# IMD.net
KiCad netlist of a schematic drawn in Altium Designer
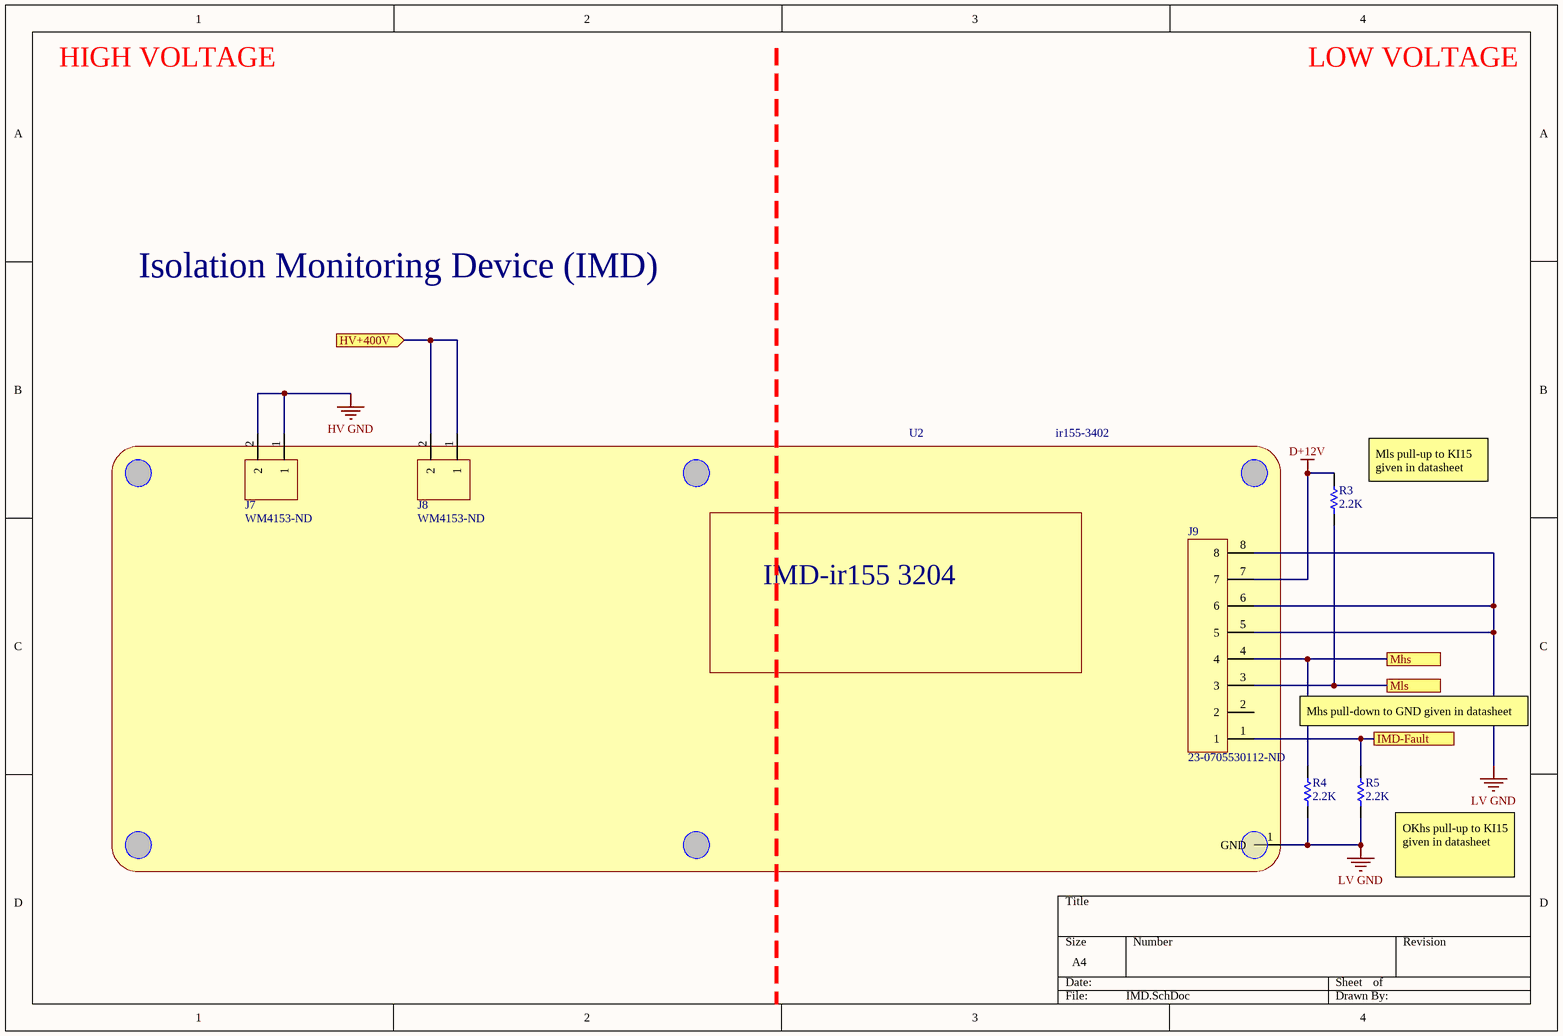
[diagram p0: IMD.SchDoc]

(export (version "E")
  (design (tool "Eeschema 10.0.6"))
  (components
    (comp (ref "J7")
      (value "WM4153-ND")
      (footprint "2PIN")
      (description "CONN HEADER R/A 2POS 2.54MM")
      (fields (field (name "MANUFACTURER") "Molex") (field (name "MANUFACTURER PART NUMBER") "0705530106"))
      (libsource (lib "Connectors") (part "2PIN"))
    )
    (comp (ref "J8")
      (value "WM4153-ND")
      (footprint "2PIN")
      (description "CONN HEADER R/A 2POS 2.54MM")
      (fields (field (name "MANUFACTURER") "Molex") (field (name "MANUFACTURER PART NUMBER") "0705530106"))
      (libsource (lib "Connectors") (part "2PIN"))
    )
    (comp (ref "J9")
      (value "23-0705530112-ND")
      (footprint "8PIN")
      (description "CONN HEADER R/A 8POS 2.54MM")
      (fields (field (name "MANUFACTURER") "Molex") (field (name "MANUFACTURER PART NUMBER") "70553-0112"))
      (libsource (lib "Connectors") (part "8PIN"))
    )
    (comp (ref "R3")
      (value "2.2K")
      (footprint "RES-0805")
      (description "RES SMD 2.2K OHM 1% 1/8W 0805")
      (fields
        (field (name "MANUFACTURER") "Yageo")
        (field (name "MANUFACTURER PART NUMBER") "RC0805FR-072K2L")
      )
      (libsource (lib "Resistors") (part "0805-2.2KR"))
    )
    (comp (ref "R4")
      (value "2.2K")
      (footprint "RES-0805")
      (description "RES SMD 2.2K OHM 1% 1/8W 0805")
      (fields
        (field (name "MANUFACTURER") "Yageo")
        (field (name "MANUFACTURER PART NUMBER") "RC0805FR-072K2L")
      )
      (libsource (lib "Resistors") (part "0805-2.2KR"))
    )
    (comp (ref "R5")
      (value "2.2K")
      (footprint "RES-0805")
      (description "RES SMD 2.2K OHM 1% 1/8W 0805")
      (fields
        (field (name "MANUFACTURER") "Yageo")
        (field (name "MANUFACTURER PART NUMBER") "RC0805FR-072K2L")
      )
      (libsource (lib "Resistors") (part "0805-2.2KR"))
    )
    (comp (ref "U2")
      (value "ir155-3402")
      (footprint "IMD-Bender ir155 3204")
      (libsource (lib "Misc") (part "IMD-ir155-3402"))
    )
  )
  (nets
    (net (code "1") (name "/HV+400V") (class "Default")
      (node (ref "J8") (pin "1") (pinfunction "1_1") (pintype "passive"))
      (node (ref "J8") (pin "2") (pinfunction "2_2") (pintype "passive"))
    )
    (net (code "2") (name "/IMD-Fault") (class "Default")
      (node (ref "J9") (pin "1") (pinfunction "1_1") (pintype "passive"))
      (node (ref "R5") (pin "2") (pinfunction "2_2") (pintype "passive"))
    )
    (net (code "3") (name "/Mhs") (class "Default")
      (node (ref "J9") (pin "4") (pinfunction "4_4") (pintype "passive"))
      (node (ref "R4") (pin "2") (pinfunction "2_2") (pintype "passive"))
    )
    (net (code "4") (name "/Mls") (class "Default")
      (node (ref "J9") (pin "3") (pinfunction "3_3") (pintype "passive"))
      (node (ref "R3") (pin "1") (pinfunction "1_1") (pintype "passive"))
    )
    (net (code "5") (name "D+12V") (class "Default")
      (node (ref "J9") (pin "7") (pinfunction "7_7") (pintype "passive"))
      (node (ref "R3") (pin "2") (pinfunction "2_2") (pintype "passive"))
    )
    (net (code "6") (name "HV GND") (class "Default")
      (node (ref "J7") (pin "1") (pinfunction "1_1") (pintype "passive"))
      (node (ref "J7") (pin "2") (pinfunction "2_2") (pintype "passive"))
    )
    (net (code "7") (name "LV GND") (class "Default")
      (node (ref "J9") (pin "5") (pinfunction "5_5") (pintype "passive"))
      (node (ref "J9") (pin "6") (pinfunction "6_6") (pintype "passive"))
      (node (ref "J9") (pin "8") (pinfunction "8_8") (pintype "passive"))
      (node (ref "R4") (pin "1") (pinfunction "1_1") (pintype "passive"))
      (node (ref "R5") (pin "1") (pinfunction "1_1") (pintype "passive"))
      (node (ref "U2") (pin "1") (pinfunction "GND_1") (pintype "passive"))
    )
    (net (code "8") (name "unconnected-(J9-Pad2)") (class "Default")
      (node (ref "J9") (pin "2") (pinfunction "2_2") (pintype "passive"))
    )
  )
)
